# MCU_MSP430F5529IPN.net
KiCad netlist of a schematic drawn in Altium Designer
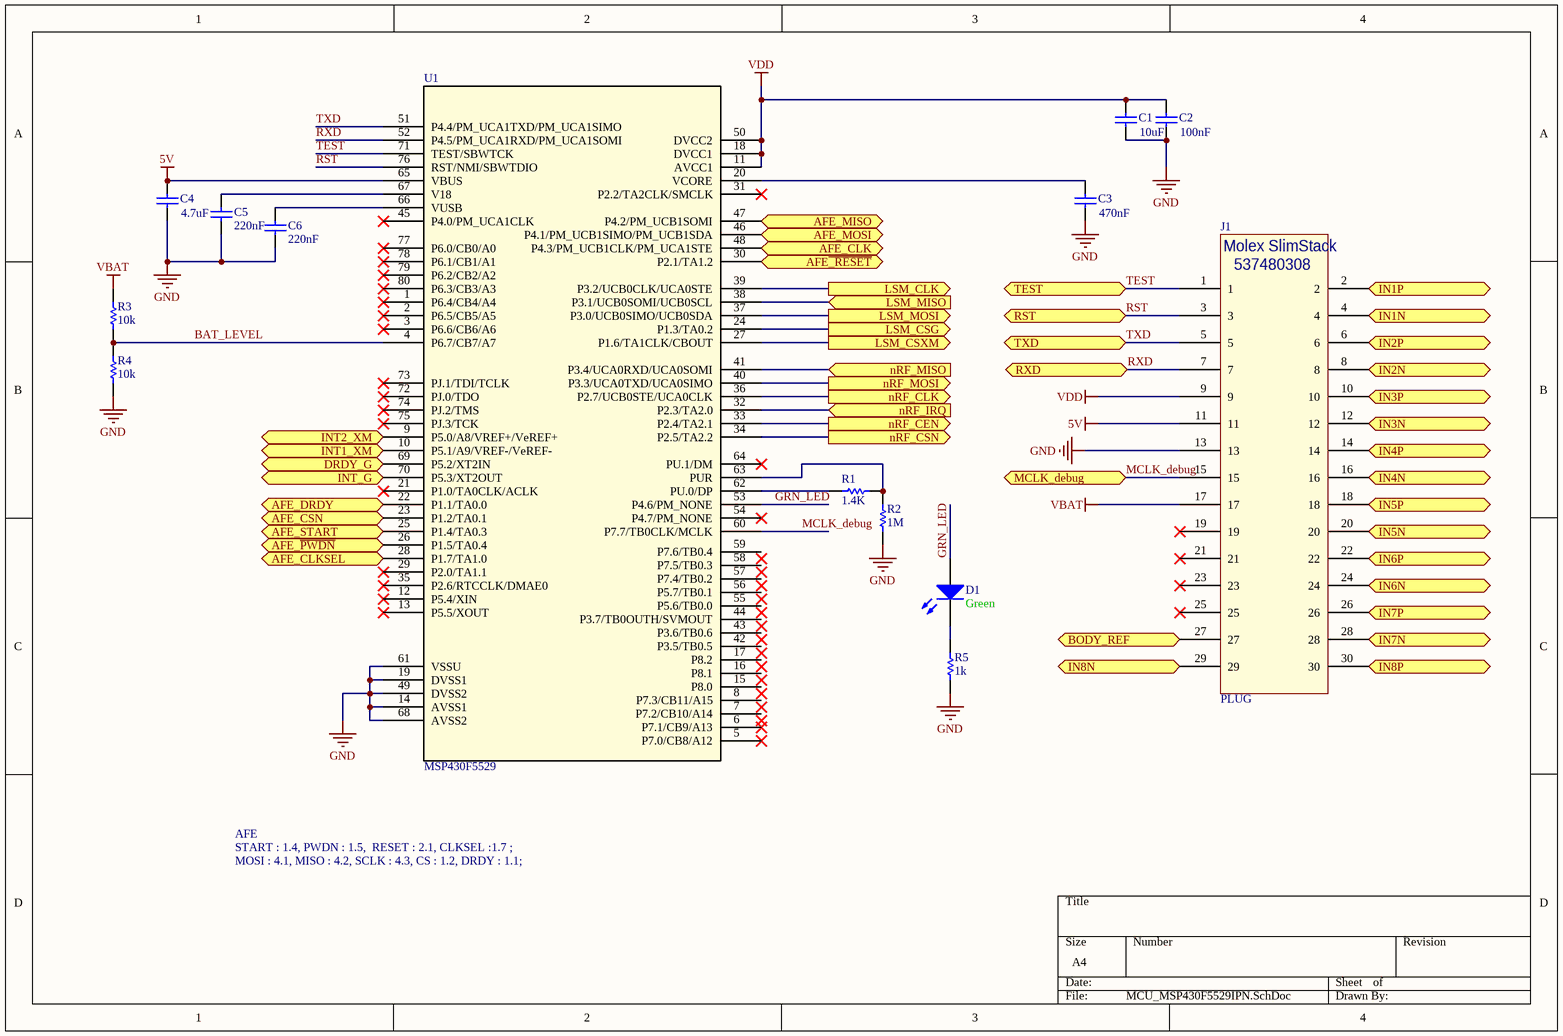
[diagram p0: MCU_MSP430F5529IPN.SchDoc]

(export (version "E")
  (design (tool "Eeschema 10.0.6"))
  (components
    (comp (ref "C1")
      (value "10uF")
      (footprint "0402")
      (description "Capacitor (Semiconductor SIM Model)")
      (fields (field (name "Comment") "Cap Semi") (field (name "PUBLISHER") "Altium Limited"))
      (libsource (lib "Miscellaneous Devices") (part "Cap Semi"))
    )
    (comp (ref "C2")
      (value "100nF")
      (footprint "0402")
      (description "Capacitor (Semiconductor SIM Model)")
      (fields (field (name "Comment") "Cap Semi") (field (name "PUBLISHER") "Altium Limited"))
      (libsource (lib "Miscellaneous Devices") (part "Cap Semi"))
    )
    (comp (ref "C3")
      (value "470nF")
      (footprint "0402")
      (description "Capacitor (Semiconductor SIM Model)")
      (fields (field (name "Comment") "Cap Semi") (field (name "PUBLISHER") "Altium Limited"))
      (libsource (lib "Miscellaneous Devices") (part "Cap Semi"))
    )
    (comp (ref "C4")
      (value "4.7uF")
      (footprint "0402")
      (description "Capacitor (Semiconductor SIM Model)")
      (fields (field (name "Comment") "Cap Semi") (field (name "PUBLISHER") "Altium Limited"))
      (libsource (lib "Miscellaneous Devices") (part "Cap Semi"))
    )
    (comp (ref "C5")
      (value "220nF")
      (footprint "0402")
      (description "Capacitor (Semiconductor SIM Model)")
      (fields (field (name "Comment") "Cap Semi") (field (name "PUBLISHER") "Altium Limited"))
      (libsource (lib "Miscellaneous Devices") (part "Cap Semi"))
    )
    (comp (ref "C6")
      (value "220nF")
      (footprint "0402")
      (description "Capacitor (Semiconductor SIM Model)")
      (fields (field (name "Comment") "Cap Semi") (field (name "PUBLISHER") "Altium Limited"))
      (libsource (lib "Miscellaneous Devices") (part "Cap Semi"))
    )
    (comp (ref "D1")
      (value "~")
      (footprint "0402")
      (description "Typical BLUE SiC LED")
      (fields (field (name "COLOR") "Green") (field (name "PUBLISHER") "Altium Limited"))
      (libsource (lib "Miscellaneous Devices") (part "LED3"))
    )
    (comp (ref "J1")
      (value "PLUG")
      (footprint "Molex 0529910308")
      (libsource (lib "Molex_0537480308_PLUG") (part "Molex 529910308"))
    )
    (comp (ref "R1")
      (value "1.4K")
      (footprint "0402")
      (description "Semiconductor Resistor")
      (fields (field (name "PUBLISHER") "Altium Limited"))
      (libsource (lib "Miscellaneous Devices") (part "Res Semi"))
    )
    (comp (ref "R2")
      (value "1M")
      (footprint "0402")
      (description "Semiconductor Resistor")
      (fields (field (name "PUBLISHER") "Altium Limited"))
      (libsource (lib "Miscellaneous Devices") (part "Res Semi"))
    )
    (comp (ref "R3")
      (value "10k")
      (footprint "0402")
      (description "Semiconductor Resistor")
      (fields (field (name "PUBLISHER") "Altium Limited"))
      (libsource (lib "Miscellaneous Devices") (part "Res Semi"))
    )
    (comp (ref "R4")
      (value "10k")
      (footprint "0402")
      (description "Semiconductor Resistor")
      (fields (field (name "PUBLISHER") "Altium Limited"))
      (libsource (lib "Miscellaneous Devices") (part "Res Semi"))
    )
    (comp (ref "R5")
      (value "1k")
      (footprint "0402")
      (description "Semiconductor Resistor")
      (fields (field (name "PUBLISHER") "Altium Limited"))
      (libsource (lib "Miscellaneous Devices") (part "Res Semi"))
    )
    (comp (ref "U1")
      (value "MSP430F5529")
      (footprint "80-LQFP")
      (description "IC MCU 16BIT 128KB FLASH 80LQFP")
      (libsource (lib "MSP430F5529IPN") (part "MSP430F5529"))
    )
  )
  (nets
    (net (code "1") (name "/AFE_CLK") (class "Default")
      (node (ref "U1") (pin "48") (pinfunction "P4.3/PM_UCB1CLK/PM_UCA1STE_48") (pintype "passive"))
    )
    (net (code "2") (name "/AFE_CLKSEL") (class "Default")
      (node (ref "U1") (pin "28") (pinfunction "P1.7/TA1.0_28") (pintype "passive"))
    )
    (net (code "3") (name "/AFE_CSN") (class "Default")
      (node (ref "U1") (pin "23") (pinfunction "P1.2/TA0.1_23") (pintype "passive"))
    )
    (net (code "4") (name "/AFE_DRDY") (class "Default")
      (node (ref "U1") (pin "22") (pinfunction "P1.1/TA0.0_22") (pintype "passive"))
    )
    (net (code "5") (name "/AFE_MISO") (class "Default")
      (node (ref "U1") (pin "47") (pinfunction "P4.2/PM_UCB1SOMI_47") (pintype "passive"))
    )
    (net (code "6") (name "/AFE_MOSI") (class "Default")
      (node (ref "U1") (pin "46") (pinfunction "P4.1/PM_UCB1SIMO/PM_UCB1SDA_46") (pintype "passive"))
    )
    (net (code "7") (name "/AFE_START") (class "Default")
      (node (ref "U1") (pin "25") (pinfunction "P1.4/TA0.3_25") (pintype "passive"))
    )
    (net (code "8") (name "/AFE_~{PWDN}") (class "Default")
      (node (ref "U1") (pin "26") (pinfunction "P1.5/TA0.4_26") (pintype "passive"))
    )
    (net (code "9") (name "/AFE~{_RESET}") (class "Default")
      (node (ref "U1") (pin "30") (pinfunction "P2.1/TA1.2_30") (pintype "passive"))
    )
    (net (code "10") (name "/BAT_LEVEL") (class "Default")
      (node (ref "R3") (pin "1") (pinfunction "1_1") (pintype "passive"))
      (node (ref "R4") (pin "2") (pinfunction "2_2") (pintype "passive"))
      (node (ref "U1") (pin "4") (pinfunction "P6.7/CB7/A7_4") (pintype "passive"))
    )
    (net (code "11") (name "/BODY_REF") (class "Default")
      (node (ref "J1") (pin "27") (pinfunction "27_27") (pintype "passive"))
    )
    (net (code "12") (name "/DRDY_G") (class "Default")
      (node (ref "U1") (pin "69") (pinfunction "P5.2/XT2IN_69") (pintype "passive"))
    )
    (net (code "13") (name "/GRN_LED") (class "Default")
      (node (ref "D1") (pin "1") (pinfunction "A_1") (pintype "passive"))
      (node (ref "U1") (pin "53") (pinfunction "P4.6/PM_NONE_53") (pintype "passive"))
    )
    (net (code "14") (name "/IN1N") (class "Default")
      (node (ref "J1") (pin "4") (pinfunction "4_4") (pintype "passive"))
    )
    (net (code "15") (name "/IN1P") (class "Default")
      (node (ref "J1") (pin "2") (pinfunction "2_2") (pintype "passive"))
    )
    (net (code "16") (name "/IN2N") (class "Default")
      (node (ref "J1") (pin "8") (pinfunction "8_8") (pintype "passive"))
    )
    (net (code "17") (name "/IN2P") (class "Default")
      (node (ref "J1") (pin "6") (pinfunction "6_6") (pintype "passive"))
    )
    (net (code "18") (name "/IN3N") (class "Default")
      (node (ref "J1") (pin "12") (pinfunction "12_12") (pintype "passive"))
    )
    (net (code "19") (name "/IN3P") (class "Default")
      (node (ref "J1") (pin "10") (pinfunction "10_10") (pintype "passive"))
    )
    (net (code "20") (name "/IN4N") (class "Default")
      (node (ref "J1") (pin "16") (pinfunction "16_16") (pintype "passive"))
    )
    (net (code "21") (name "/IN4P") (class "Default")
      (node (ref "J1") (pin "14") (pinfunction "14_14") (pintype "passive"))
    )
    (net (code "22") (name "/IN5N") (class "Default")
      (node (ref "J1") (pin "20") (pinfunction "20_20") (pintype "passive"))
    )
    (net (code "23") (name "/IN5P") (class "Default")
      (node (ref "J1") (pin "18") (pinfunction "18_18") (pintype "passive"))
    )
    (net (code "24") (name "/IN6N") (class "Default")
      (node (ref "J1") (pin "24") (pinfunction "24_24") (pintype "passive"))
    )
    (net (code "25") (name "/IN6P") (class "Default")
      (node (ref "J1") (pin "22") (pinfunction "22_22") (pintype "passive"))
    )
    (net (code "26") (name "/IN7N") (class "Default")
      (node (ref "J1") (pin "28") (pinfunction "28_28") (pintype "passive"))
    )
    (net (code "27") (name "/IN7P") (class "Default")
      (node (ref "J1") (pin "26") (pinfunction "26_26") (pintype "passive"))
    )
    (net (code "28") (name "/IN8N") (class "Default")
      (node (ref "J1") (pin "29") (pinfunction "29_29") (pintype "passive"))
    )
    (net (code "29") (name "/IN8P") (class "Default")
      (node (ref "J1") (pin "30") (pinfunction "30_30") (pintype "passive"))
    )
    (net (code "30") (name "/INT1_XM") (class "Default")
      (node (ref "U1") (pin "10") (pinfunction "P5.1/A9/VREF-/VeREF-_10") (pintype "passive"))
    )
    (net (code "31") (name "/INT2_XM") (class "Default")
      (node (ref "U1") (pin "9") (pinfunction "P5.0/A8/VREF+/VeREF+_9") (pintype "passive"))
    )
    (net (code "32") (name "/INT_G") (class "Default")
      (node (ref "U1") (pin "70") (pinfunction "P5.3/XT2OUT_70") (pintype "passive"))
    )
    (net (code "33") (name "/LSM_CLK") (class "Default")
      (node (ref "U1") (pin "39") (pinfunction "P3.2/UCB0CLK/UCA0STE_39") (pintype "passive"))
    )
    (net (code "34") (name "/LSM_CSG") (class "Default")
      (node (ref "U1") (pin "24") (pinfunction "P1.3/TA0.2_24") (pintype "passive"))
    )
    (net (code "35") (name "/LSM_CSXM") (class "Default")
      (node (ref "U1") (pin "27") (pinfunction "P1.6/TA1CLK/CBOUT_27") (pintype "passive"))
    )
    (net (code "36") (name "/LSM_MISO") (class "Default")
      (node (ref "U1") (pin "38") (pinfunction "P3.1/UCB0SOMI/UCB0SCL_38") (pintype "passive"))
    )
    (net (code "37") (name "/LSM_MOSI") (class "Default")
      (node (ref "U1") (pin "37") (pinfunction "P3.0/UCB0SIMO/UCB0SDA_37") (pintype "passive"))
    )
    (net (code "38") (name "/MCLK_debug") (class "Default")
      (node (ref "J1") (pin "15") (pinfunction "15_15") (pintype "passive"))
      (node (ref "U1") (pin "60") (pinfunction "P7.7/TB0CLK/MCLK_60") (pintype "passive"))
    )
    (net (code "39") (name "/RST") (class "Default")
      (node (ref "J1") (pin "3") (pinfunction "3_3") (pintype "passive"))
      (node (ref "U1") (pin "76") (pinfunction "RST/NMI/SBWTDIO_76") (pintype "passive"))
    )
    (net (code "40") (name "/RXD") (class "Default")
      (node (ref "J1") (pin "7") (pinfunction "7_7") (pintype "passive"))
      (node (ref "U1") (pin "52") (pinfunction "P4.5/PM_UCA1RXD/PM_UCA1SOMI_52") (pintype "passive"))
    )
    (net (code "41") (name "/TEST") (class "Default")
      (node (ref "J1") (pin "1") (pinfunction "1_1") (pintype "passive"))
      (node (ref "U1") (pin "71") (pinfunction "TEST/SBWTCK_71") (pintype "passive"))
    )
    (net (code "42") (name "/TXD") (class "Default")
      (node (ref "J1") (pin "5") (pinfunction "5_5") (pintype "passive"))
      (node (ref "U1") (pin "51") (pinfunction "P4.4/PM_UCA1TXD/PM_UCA1SIMO_51") (pintype "passive"))
    )
    (net (code "43") (name "/nRF_CEN") (class "Default")
      (node (ref "U1") (pin "33") (pinfunction "P2.4/TA2.1_33") (pintype "passive"))
    )
    (net (code "44") (name "/nRF_CLK") (class "Default")
      (node (ref "U1") (pin "36") (pinfunction "P2.7/UCB0STE/UCA0CLK_36") (pintype "passive"))
    )
    (net (code "45") (name "/nRF_CSN") (class "Default")
      (node (ref "U1") (pin "34") (pinfunction "P2.5/TA2.2_34") (pintype "passive"))
    )
    (net (code "46") (name "/nRF_IRQ") (class "Default")
      (node (ref "U1") (pin "32") (pinfunction "P2.3/TA2.0_32") (pintype "passive"))
    )
    (net (code "47") (name "/nRF_MISO") (class "Default")
      (node (ref "U1") (pin "41") (pinfunction "P3.4/UCA0RXD/UCA0SOMI_41") (pintype "passive"))
    )
    (net (code "48") (name "/nRF_MOSI") (class "Default")
      (node (ref "U1") (pin "40") (pinfunction "P3.3/UCA0TXD/UCA0SIMO_40") (pintype "passive"))
    )
    (net (code "49") (name "5V") (class "Default")
      (node (ref "C4") (pin "1") (pinfunction "1_1") (pintype "passive"))
      (node (ref "J1") (pin "11") (pinfunction "11_11") (pintype "passive"))
      (node (ref "U1") (pin "65") (pinfunction "VBUS_65") (pintype "passive"))
    )
    (net (code "50") (name "GND") (class "Default")
      (node (ref "C1") (pin "2") (pinfunction "2_2") (pintype "passive"))
      (node (ref "C2") (pin "2") (pinfunction "2_2") (pintype "passive"))
      (node (ref "C3") (pin "2") (pinfunction "2_2") (pintype "passive"))
      (node (ref "C4") (pin "2") (pinfunction "2_2") (pintype "passive"))
      (node (ref "C5") (pin "1") (pinfunction "1_1") (pintype "passive"))
      (node (ref "C6") (pin "1") (pinfunction "1_1") (pintype "passive"))
      (node (ref "J1") (pin "13") (pinfunction "13_13") (pintype "passive"))
      (node (ref "R2") (pin "2") (pinfunction "2_2") (pintype "passive"))
      (node (ref "R4") (pin "1") (pinfunction "1_1") (pintype "passive"))
      (node (ref "R5") (pin "2") (pinfunction "2_2") (pintype "passive"))
      (node (ref "U1") (pin "14") (pinfunction "AVSS1_14") (pintype "passive"))
      (node (ref "U1") (pin "19") (pinfunction "DVSS1_19") (pintype "passive"))
      (node (ref "U1") (pin "49") (pinfunction "DVSS2_49") (pintype "passive"))
      (node (ref "U1") (pin "61") (pinfunction "VSSU_61") (pintype "passive"))
      (node (ref "U1") (pin "68") (pinfunction "AVSS2_68") (pintype "passive"))
    )
    (net (code "51") (name "Net-(D1-K)") (class "Default")
      (node (ref "D1") (pin "2") (pinfunction "K_2") (pintype "passive"))
      (node (ref "R5") (pin "1") (pinfunction "1_1") (pintype "passive"))
    )
    (net (code "52") (name "Net-(U1-PU.0{slash}DP)") (class "Default")
      (node (ref "R1") (pin "2") (pinfunction "2_2") (pintype "passive"))
      (node (ref "U1") (pin "62") (pinfunction "PU.0/DP_62") (pintype "passive"))
    )
    (net (code "53") (name "Net-(U1-PUR)") (class "Default")
      (node (ref "R1") (pin "1") (pinfunction "1_1") (pintype "passive"))
      (node (ref "R2") (pin "1") (pinfunction "1_1") (pintype "passive"))
      (node (ref "U1") (pin "63") (pinfunction "PUR_63") (pintype "passive"))
    )
    (net (code "54") (name "Net-(U1-V18)") (class "Default")
      (node (ref "C5") (pin "2") (pinfunction "2_2") (pintype "passive"))
      (node (ref "U1") (pin "67") (pinfunction "V18_67") (pintype "passive"))
    )
    (net (code "55") (name "Net-(U1-VCORE)") (class "Default")
      (node (ref "C3") (pin "1") (pinfunction "1_1") (pintype "passive"))
      (node (ref "U1") (pin "20") (pinfunction "VCORE_20") (pintype "passive"))
    )
    (net (code "56") (name "Net-(U1-VUSB)") (class "Default")
      (node (ref "C6") (pin "2") (pinfunction "2_2") (pintype "passive"))
      (node (ref "U1") (pin "66") (pinfunction "VUSB_66") (pintype "passive"))
    )
    (net (code "57") (name "VBAT") (class "Default")
      (node (ref "J1") (pin "17") (pinfunction "17_17") (pintype "passive"))
      (node (ref "R3") (pin "2") (pinfunction "2_2") (pintype "passive"))
    )
    (net (code "58") (name "VDD") (class "Default")
      (node (ref "C1") (pin "1") (pinfunction "1_1") (pintype "passive"))
      (node (ref "C2") (pin "1") (pinfunction "1_1") (pintype "passive"))
      (node (ref "J1") (pin "9") (pinfunction "9_9") (pintype "passive"))
      (node (ref "U1") (pin "11") (pinfunction "AVCC1_11") (pintype "passive"))
      (node (ref "U1") (pin "18") (pinfunction "DVCC1_18") (pintype "passive"))
      (node (ref "U1") (pin "50") (pinfunction "DVCC2_50") (pintype "passive"))
    )
    (net (code "59") (name "unconnected-(J1-Pad19)") (class "Default")
      (node (ref "J1") (pin "19") (pinfunction "19_19") (pintype "passive+no_connect"))
    )
    (net (code "60") (name "unconnected-(J1-Pad21)") (class "Default")
      (node (ref "J1") (pin "21") (pinfunction "21_21") (pintype "passive+no_connect"))
    )
    (net (code "61") (name "unconnected-(J1-Pad23)") (class "Default")
      (node (ref "J1") (pin "23") (pinfunction "23_23") (pintype "passive+no_connect"))
    )
    (net (code "62") (name "unconnected-(J1-Pad25)") (class "Default")
      (node (ref "J1") (pin "25") (pinfunction "25_25") (pintype "passive+no_connect"))
    )
    (net (code "63") (name "unconnected-(U1-P1.0{slash}TA0CLK{slash}ACLK-Pad21)") (class "Default")
      (node (ref "U1") (pin "21") (pinfunction "P1.0/TA0CLK/ACLK_21") (pintype "passive+no_connect"))
    )
    (net (code "64") (name "unconnected-(U1-P2.0{slash}TA1.1-Pad29)") (class "Default")
      (node (ref "U1") (pin "29") (pinfunction "P2.0/TA1.1_29") (pintype "passive+no_connect"))
    )
    (net (code "65") (name "unconnected-(U1-P2.2{slash}TA2CLK{slash}SMCLK-Pad31)") (class "Default")
      (node (ref "U1") (pin "31") (pinfunction "P2.2/TA2CLK/SMCLK_31") (pintype "passive+no_connect"))
    )
    (net (code "66") (name "unconnected-(U1-P2.6{slash}RTCCLK{slash}DMAE0-Pad35)") (class "Default")
      (node (ref "U1") (pin "35") (pinfunction "P2.6/RTCCLK/DMAE0_35") (pintype "passive+no_connect"))
    )
    (net (code "67") (name "unconnected-(U1-P3.5{slash}TB0.5-Pad42)") (class "Default")
      (node (ref "U1") (pin "42") (pinfunction "P3.5/TB0.5_42") (pintype "passive"))
    )
    (net (code "68") (name "unconnected-(U1-P3.6{slash}TB0.6-Pad43)") (class "Default")
      (node (ref "U1") (pin "43") (pinfunction "P3.6/TB0.6_43") (pintype "passive"))
    )
    (net (code "69") (name "unconnected-(U1-P3.7{slash}TB0OUTH{slash}SVMOUT-Pad44)") (class "Default")
      (node (ref "U1") (pin "44") (pinfunction "P3.7/TB0OUTH/SVMOUT_44") (pintype "passive"))
    )
    (net (code "70") (name "unconnected-(U1-P4.0{slash}PM_UCA1CLK-Pad45)") (class "Default")
      (node (ref "U1") (pin "45") (pinfunction "P4.0/PM_UCA1CLK_45") (pintype "passive+no_connect"))
    )
    (net (code "71") (name "unconnected-(U1-P4.7{slash}PM_NONE-Pad54)") (class "Default")
      (node (ref "U1") (pin "54") (pinfunction "P4.7/PM_NONE_54") (pintype "passive+no_connect"))
    )
    (net (code "72") (name "unconnected-(U1-P5.4{slash}XIN-Pad12)") (class "Default")
      (node (ref "U1") (pin "12") (pinfunction "P5.4/XIN_12") (pintype "passive+no_connect"))
    )
    (net (code "73") (name "unconnected-(U1-P5.5{slash}XOUT-Pad13)") (class "Default")
      (node (ref "U1") (pin "13") (pinfunction "P5.5/XOUT_13") (pintype "passive+no_connect"))
    )
    (net (code "74") (name "unconnected-(U1-P5.6{slash}TB0.0-Pad55)") (class "Default")
      (node (ref "U1") (pin "55") (pinfunction "P5.6/TB0.0_55") (pintype "passive"))
    )
    (net (code "75") (name "unconnected-(U1-P5.7{slash}TB0.1-Pad56)") (class "Default")
      (node (ref "U1") (pin "56") (pinfunction "P5.7/TB0.1_56") (pintype "passive"))
    )
    (net (code "76") (name "unconnected-(U1-P6.0{slash}CB0{slash}A0-Pad77)") (class "Default")
      (node (ref "U1") (pin "77") (pinfunction "P6.0/CB0/A0_77") (pintype "passive+no_connect"))
    )
    (net (code "77") (name "unconnected-(U1-P6.1{slash}CB1{slash}A1-Pad78)") (class "Default")
      (node (ref "U1") (pin "78") (pinfunction "P6.1/CB1/A1_78") (pintype "passive+no_connect"))
    )
    (net (code "78") (name "unconnected-(U1-P6.2{slash}CB2{slash}A2-Pad79)") (class "Default")
      (node (ref "U1") (pin "79") (pinfunction "P6.2/CB2/A2_79") (pintype "passive+no_connect"))
    )
    (net (code "79") (name "unconnected-(U1-P6.3{slash}CB3{slash}A3-Pad80)") (class "Default")
      (node (ref "U1") (pin "80") (pinfunction "P6.3/CB3/A3_80") (pintype "passive+no_connect"))
    )
    (net (code "80") (name "unconnected-(U1-P6.4{slash}CB4{slash}A4-Pad1)") (class "Default")
      (node (ref "U1") (pin "1") (pinfunction "P6.4/CB4/A4_1") (pintype "passive+no_connect"))
    )
    (net (code "81") (name "unconnected-(U1-P6.5{slash}CB5{slash}A5-Pad2)") (class "Default")
      (node (ref "U1") (pin "2") (pinfunction "P6.5/CB5/A5_2") (pintype "passive+no_connect"))
    )
    (net (code "82") (name "unconnected-(U1-P6.6{slash}CB6{slash}A6-Pad3)") (class "Default")
      (node (ref "U1") (pin "3") (pinfunction "P6.6/CB6/A6_3") (pintype "passive+no_connect"))
    )
    (net (code "83") (name "unconnected-(U1-P7.0{slash}CB8{slash}A12-Pad5)") (class "Default")
      (node (ref "U1") (pin "5") (pinfunction "P7.0/CB8/A12_5") (pintype "passive+no_connect"))
    )
    (net (code "84") (name "unconnected-(U1-P7.1{slash}CB9{slash}A13-Pad6)") (class "Default")
      (node (ref "U1") (pin "6") (pinfunction "P7.1/CB9/A13_6") (pintype "passive+no_connect"))
    )
    (net (code "85") (name "unconnected-(U1-P7.2{slash}CB10{slash}A14-Pad7)") (class "Default")
      (node (ref "U1") (pin "7") (pinfunction "P7.2/CB10/A14_7") (pintype "passive"))
    )
    (net (code "86") (name "unconnected-(U1-P7.3{slash}CB11{slash}A15-Pad8)") (class "Default")
      (node (ref "U1") (pin "8") (pinfunction "P7.3/CB11/A15_8") (pintype "passive"))
    )
    (net (code "87") (name "unconnected-(U1-P7.4{slash}TB0.2-Pad57)") (class "Default")
      (node (ref "U1") (pin "57") (pinfunction "P7.4/TB0.2_57") (pintype "passive"))
    )
    (net (code "88") (name "unconnected-(U1-P7.5{slash}TB0.3-Pad58)") (class "Default")
      (node (ref "U1") (pin "58") (pinfunction "P7.5/TB0.3_58") (pintype "passive"))
    )
    (net (code "89") (name "unconnected-(U1-P7.6{slash}TB0.4-Pad59)") (class "Default")
      (node (ref "U1") (pin "59") (pinfunction "P7.6/TB0.4_59") (pintype "passive"))
    )
    (net (code "90") (name "unconnected-(U1-P8.0-Pad15)") (class "Default")
      (node (ref "U1") (pin "15") (pinfunction "P8.0_15") (pintype "passive"))
    )
    (net (code "91") (name "unconnected-(U1-P8.1-Pad16)") (class "Default")
      (node (ref "U1") (pin "16") (pinfunction "P8.1_16") (pintype "passive"))
    )
    (net (code "92") (name "unconnected-(U1-P8.2-Pad17)") (class "Default")
      (node (ref "U1") (pin "17") (pinfunction "P8.2_17") (pintype "passive"))
    )
    (net (code "93") (name "unconnected-(U1-PJ.0{slash}TDO-Pad72)") (class "Default")
      (node (ref "U1") (pin "72") (pinfunction "PJ.0/TDO_72") (pintype "passive+no_connect"))
    )
    (net (code "94") (name "unconnected-(U1-PJ.1{slash}TDI{slash}TCLK-Pad73)") (class "Default")
      (node (ref "U1") (pin "73") (pinfunction "PJ.1/TDI/TCLK_73") (pintype "passive+no_connect"))
    )
    (net (code "95") (name "unconnected-(U1-PJ.2{slash}TMS-Pad74)") (class "Default")
      (node (ref "U1") (pin "74") (pinfunction "PJ.2/TMS_74") (pintype "passive+no_connect"))
    )
    (net (code "96") (name "unconnected-(U1-PJ.3{slash}TCK-Pad75)") (class "Default")
      (node (ref "U1") (pin "75") (pinfunction "PJ.3/TCK_75") (pintype "passive+no_connect"))
    )
    (net (code "97") (name "unconnected-(U1-PU.1{slash}DM-Pad64)") (class "Default")
      (node (ref "U1") (pin "64") (pinfunction "PU.1/DM_64") (pintype "passive+no_connect"))
    )
  )
)
